# Sheet1.net
KiCad netlist of a schematic drawn in Altium Designer
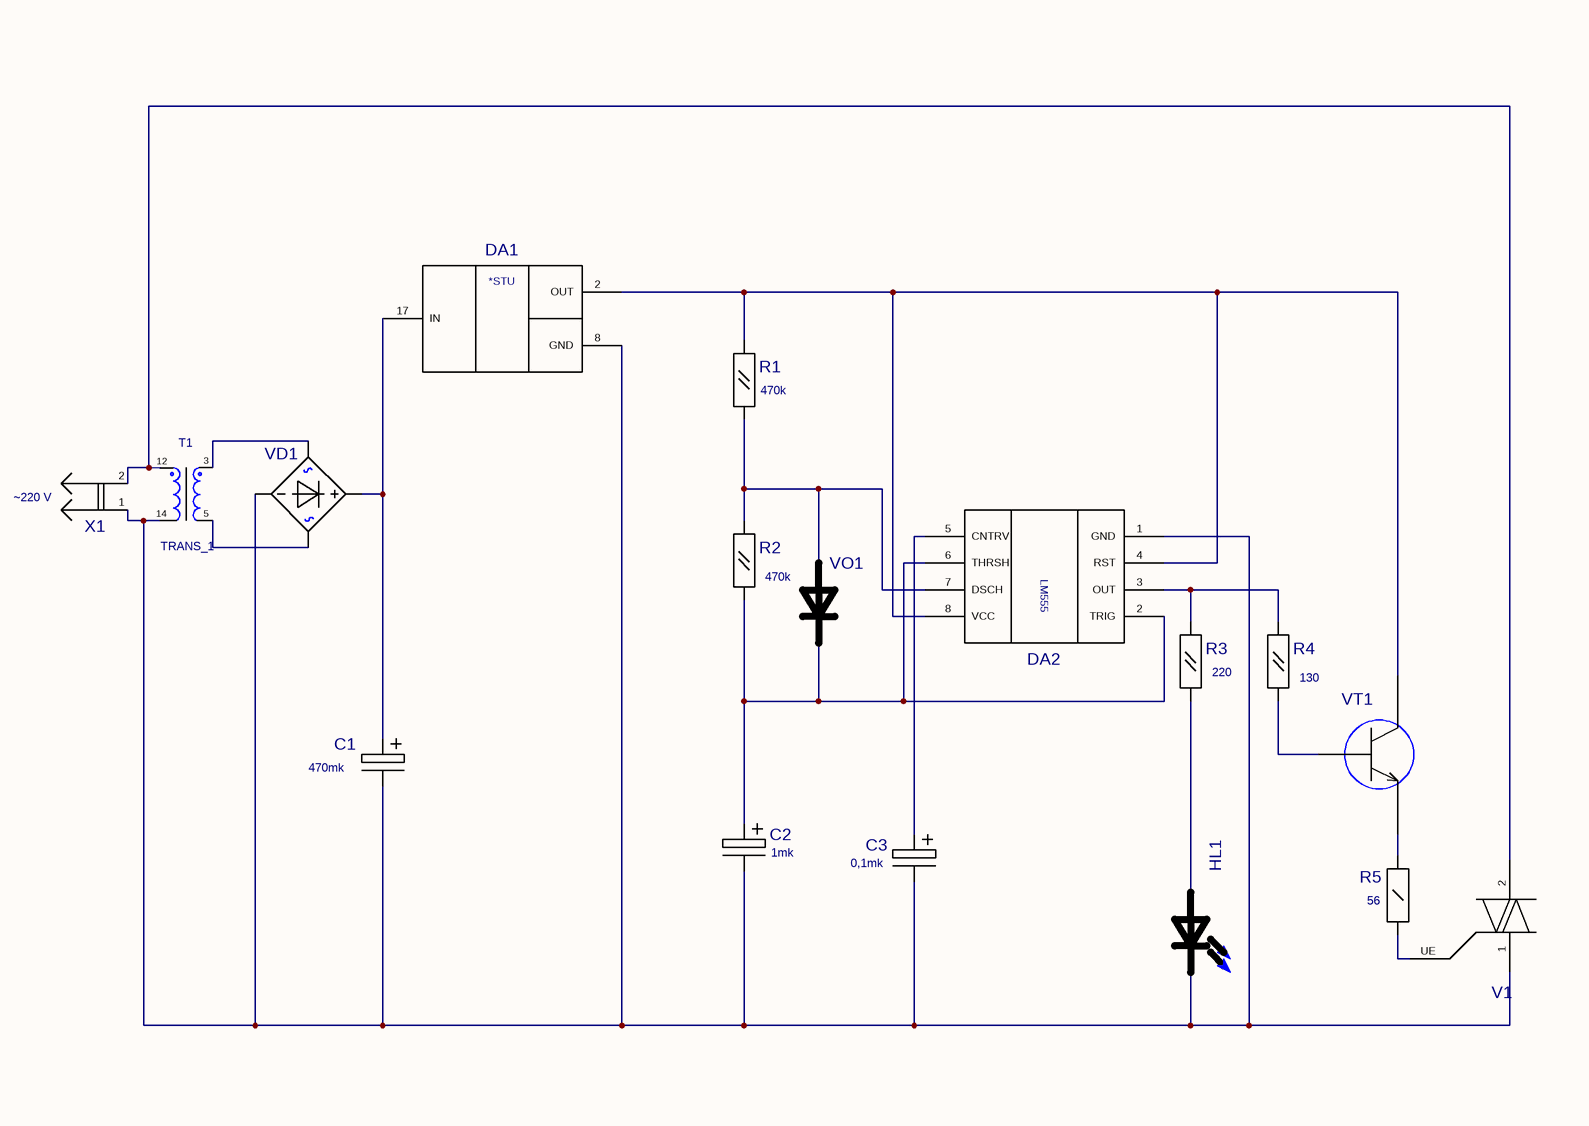
[diagram p0: Sheet1.SCHDOC]

(export (version "E")
  (design (tool "Eeschema 10.0.6"))
  (components
    (comp (ref "C1")
      (value "470mk")
      (footprint "R50-35-08XX")
      (description "К50-35-470МКФ-10В")
      (libsource (lib "*") (part "К50-35-470МКФ-10В"))
    )
    (comp (ref "C2")
      (value "1mk")
      (footprint "К50-35-0511")
      (description "К50-35-1МКФ-50В")
      (libsource (lib "*") (part "К50-35-1МКФ-50В"))
    )
    (comp (ref "C3")
      (value "0,1mk")
      (footprint "К50-35-0511")
      (description "К50-35-0,1МКФ-50В")
      (libsource (lib "*") (part "К50-35-0,1МКФ-50В"))
    )
    (comp (ref "DA1")
      (value "КР142ЕН5А")
      (footprint "TO-220-KT-28-2")
      (libsource (lib "*") (part "КР142ЕН5А"))
    )
    (comp (ref "DA2") (value "LM555CM") (footprint "SO-8") (libsource (lib "*") (part "LM555CM")))
    (comp (ref "HL1") (value "ИПД156") (footprint "3528") (libsource (lib "*") (part "ИПД156")))
    (comp (ref "R1")
      (value "470k")
      (footprint "C2-33H-0.125W")
      (description "C2-33H-0.125W_OLD_UGO")
      (fields (field (name "AUTOR") "pcbdesigner.ru"))
      (libsource (lib "*") (part "C2-33H-0.125W_OLD_UGO"))
    )
    (comp (ref "R2")
      (value "470k")
      (footprint "C2-33H-0.125W")
      (description "C2-33H-0.125W_OLD_UGO")
      (fields (field (name "AUTOR") "pcbdesigner.ru"))
      (libsource (lib "*") (part "C2-33H-0.125W_OLD_UGO"))
    )
    (comp (ref "R3")
      (value "220")
      (footprint "C2-33H-0.125W")
      (description "C2-33H-0.125W_OLD_UGO")
      (fields (field (name "AUTOR") "pcbdesigner.ru"))
      (libsource (lib "*") (part "C2-33H-0.125W_OLD_UGO"))
    )
    (comp (ref "R4")
      (value "130")
      (footprint "C2-33H-0.125W")
      (description "C2-33H-0.125W_OLD_UGO")
      (fields (field (name "AUTOR") "pcbdesigner.ru"))
      (libsource (lib "*") (part "C2-33H-0.125W_OLD_UGO"))
    )
    (comp (ref "R5")
      (value "56")
      (footprint "C2-33H-0.25W")
      (description "C2-33H-0.25W_OLD_UGO")
      (fields (field (name "AUTOR") "pcbdesigner.ru"))
      (libsource (lib "*") (part "C2-33H-0.25W_OLD_UGO"))
    )
    (comp (ref "T1") (value "TRANS_1") (footprint "TRANS_1") (libsource (lib "*") (part "TRANS_1")))
    (comp (ref "V1") (value "TC122") (footprint "TC122") (libsource (lib "*") (part "TC122")))
    (comp (ref "VD1") (value "2Д2136АС") (footprint "2Д2136АС") (libsource (lib "*") (part "2Д2136АС")))
    (comp (ref "VO1") (value "1N34") (footprint "DO-7") (libsource (lib "*") (part "1N34")))
    (comp (ref "VT1") (value "КТ315Б") (footprint "KT13") (libsource (lib "*") (part "КТ315Б")))
    (comp (ref "X1")
      (value "~220 V")
      (footprint "2XR")
      (description "2XR")
      (libsource (lib "*") (part "2XR"))
    )
  )
  (nets
    (net (code "1") (name "Net-(DA1-GND)") (class "Default")
      (node (ref "C1") (pin "2") (pinfunction "2_2") (pintype "passive"))
      (node (ref "C2") (pin "2") (pinfunction "2_2") (pintype "passive"))
      (node (ref "C3") (pin "2") (pinfunction "2_2") (pintype "passive"))
      (node (ref "DA1") (pin "8") (pinfunction "GND_8") (pintype "passive"))
      (node (ref "DA2") (pin "1") (pinfunction "GND_1") (pintype "passive"))
      (node (ref "HL1") (pin "1") (pinfunction "K_1") (pintype "passive"))
      (node (ref "T1") (pin "14") (pinfunction "14_14") (pintype "passive"))
      (node (ref "V1") (pin "1") (pinfunction "E2_1") (pintype "passive"))
      (node (ref "VD1") (pin "4") (pinfunction "-_4") (pintype "passive"))
      (node (ref "X1") (pin "1") (pinfunction "I/O1_1") (pintype "passive"))
    )
    (net (code "2") (name "Net-(DA1-IN)") (class "Default")
      (node (ref "C1") (pin "1") (pinfunction "1_1") (pintype "passive"))
      (node (ref "DA1") (pin "17") (pinfunction "IN_17") (pintype "passive"))
      (node (ref "VD1") (pin "5") (pinfunction "+_5") (pintype "passive"))
    )
    (net (code "3") (name "Net-(DA1-OUT)") (class "Default")
      (node (ref "DA1") (pin "2") (pinfunction "OUT_2") (pintype "passive"))
      (node (ref "DA2") (pin "4") (pinfunction "RST_4") (pintype "passive"))
      (node (ref "DA2") (pin "8") (pinfunction "VCC_8") (pintype "passive"))
      (node (ref "R1") (pin "1") (pinfunction "1_1") (pintype "passive"))
      (node (ref "VT1") (pin "3") (pinfunction "K_3") (pintype "passive"))
    )
    (net (code "4") (name "Net-(DA2-CNTRV)") (class "Default")
      (node (ref "C3") (pin "1") (pinfunction "1_1") (pintype "passive"))
      (node (ref "DA2") (pin "5") (pinfunction "CNTRV_5") (pintype "passive"))
    )
    (net (code "5") (name "Net-(DA2-DSCH)") (class "Default")
      (node (ref "DA2") (pin "7") (pinfunction "DSCH_7") (pintype "passive"))
      (node (ref "R1") (pin "2") (pinfunction "2_2") (pintype "passive"))
      (node (ref "R2") (pin "2") (pinfunction "2_2") (pintype "passive"))
      (node (ref "VO1") (pin "A") (pinfunction "A_A") (pintype "passive"))
    )
    (net (code "6") (name "Net-(DA2-OUT)") (class "Default")
      (node (ref "DA2") (pin "3") (pinfunction "OUT_3") (pintype "passive"))
      (node (ref "R3") (pin "2") (pinfunction "2_2") (pintype "passive"))
      (node (ref "R4") (pin "2") (pinfunction "2_2") (pintype "passive"))
    )
    (net (code "7") (name "Net-(DA2-THRSH)") (class "Default")
      (node (ref "C2") (pin "1") (pinfunction "1_1") (pintype "passive"))
      (node (ref "DA2") (pin "2") (pinfunction "TRIG_2") (pintype "passive"))
      (node (ref "DA2") (pin "6") (pinfunction "THRSH_6") (pintype "passive"))
      (node (ref "R2") (pin "1") (pinfunction "1_1") (pintype "passive"))
      (node (ref "VO1") (pin "K") (pinfunction "K_K") (pintype "passive"))
    )
    (net (code "8") (name "Net-(HL1-A)") (class "Default")
      (node (ref "HL1") (pin "2") (pinfunction "A_2") (pintype "passive"))
      (node (ref "R3") (pin "1") (pinfunction "1_1") (pintype "passive"))
    )
    (net (code "9") (name "Net-(R5-Pad1)") (class "Default")
      (node (ref "R5") (pin "1") (pinfunction "1_1") (pintype "passive"))
      (node (ref "V1") (pin "UE") (pinfunction "UE_UE") (pintype "passive"))
    )
    (net (code "10") (name "Net-(T1-Pad3)") (class "Default")
      (node (ref "T1") (pin "3") (pinfunction "3_3") (pintype "passive"))
      (node (ref "VD1") (pin "1") (pintype "passive"))
    )
    (net (code "11") (name "Net-(T1-Pad5)") (class "Default")
      (node (ref "T1") (pin "5") (pinfunction "5_5") (pintype "passive"))
      (node (ref "VD1") (pin "3") (pintype "passive"))
    )
    (net (code "12") (name "Net-(V1-E1)") (class "Default")
      (node (ref "T1") (pin "12") (pinfunction "12_12") (pintype "passive"))
      (node (ref "V1") (pin "2") (pinfunction "E1_2") (pintype "passive"))
      (node (ref "X1") (pin "2") (pinfunction "I/O2_2") (pintype "passive"))
    )
    (net (code "13") (name "Net-(VT1-B)") (class "Default")
      (node (ref "R4") (pin "1") (pinfunction "1_1") (pintype "passive"))
      (node (ref "VT1") (pin "2") (pinfunction "B_2") (pintype "passive"))
    )
    (net (code "14") (name "Net-(VT1-E)") (class "Default")
      (node (ref "R5") (pin "2") (pinfunction "2_2") (pintype "passive"))
      (node (ref "VT1") (pin "1") (pinfunction "E_1") (pintype "passive"))
    )
    (net (code "15") (name "unconnected-(DA1-Pad4)") (class "Default")
      (node (ref "DA1") (pin "4") (pintype "passive"))
    )
    (net (code "16") (name "unconnected-(V1-Pad4)") (class "Default")
      (node (ref "V1") (pin "4") (pintype "passive"))
    )
    (net (code "17") (name "unconnected-(V1-Pad5)") (class "Default")
      (node (ref "V1") (pin "5") (pintype "passive"))
    )
    (net (code "18") (name "unconnected-(VD1-Pad2)") (class "Default")
      (node (ref "VD1") (pin "2") (pintype "passive"))
    )
  )
)
